# smoggie.net
KiCad netlist of a schematic drawn in EAGLE
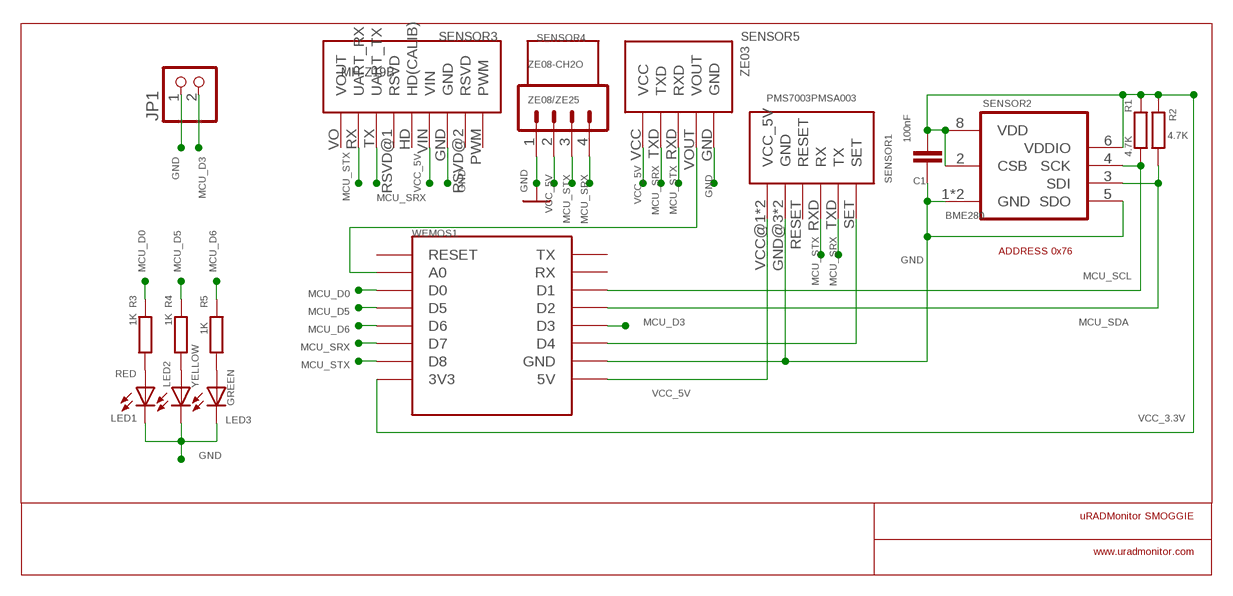
[diagram p0: schematic, sheet 1]

(export (version "E")
  (design (tool "Eeschema 10.0.6"))
  (components
    (comp (ref "C1")
      (value "100nF")
      (footprint "eagle-import:C0603")
      (libsource (lib "eagle-import") (part "C-EUC0603"))
    )
    (comp (ref "JP1")
      (value "PINHD-1X2")
      (footprint "eagle-import:1X02")
      (libsource (lib "eagle-import") (part "PINHD-1X2"))
    )
    (comp (ref "LED1")
      (value "RED")
      (footprint "eagle-import:SML0603")
      (libsource (lib "eagle-import") (part "LEDSML0603"))
    )
    (comp (ref "LED2")
      (value "YELLOW")
      (footprint "eagle-import:SML0603")
      (libsource (lib "eagle-import") (part "LEDSML0603"))
    )
    (comp (ref "LED3")
      (value "GREEN")
      (footprint "eagle-import:SML0603")
      (libsource (lib "eagle-import") (part "LEDSML0603"))
    )
    (comp (ref "R1")
      (value "4.7K")
      (footprint "eagle-import:R0603")
      (libsource (lib "eagle-import") (part "R-EU_R0603"))
    )
    (comp (ref "R2")
      (value "4.7K")
      (footprint "eagle-import:R0603")
      (libsource (lib "eagle-import") (part "R-EU_R0603"))
    )
    (comp (ref "R3")
      (value "1K")
      (footprint "eagle-import:R0603")
      (libsource (lib "eagle-import") (part "R-EU_R0603"))
    )
    (comp (ref "R4")
      (value "1K")
      (footprint "eagle-import:R0603")
      (libsource (lib "eagle-import") (part "R-EU_R0603"))
    )
    (comp (ref "R5")
      (value "1K")
      (footprint "eagle-import:R0603")
      (libsource (lib "eagle-import") (part "R-EU_R0603"))
    )
    (comp (ref "SENSOR1")
      (value "PMS7003PMSA003")
      (footprint "eagle-import:PMSA003")
      (libsource (lib "eagle-import") (part "PMS7003PMSA003"))
    )
    (comp (ref "SENSOR2")
      (value "BME280")
      (footprint "eagle-import:BME280")
      (libsource (lib "eagle-import") (part "BME280"))
    )
    (comp (ref "SENSOR3")
      (value "MH-Z19B")
      (footprint "eagle-import:MH-Z19B")
      (libsource (lib "eagle-import") (part "MH-Z19B"))
    )
    (comp (ref "SENSOR4")
      (value "ZE08-CH2O")
      (footprint "eagle-import:ZE08-CH2O_SENSOR")
      (libsource (lib "eagle-import") (part "ZE08-CH2O_SENSOR"))
    )
    (comp (ref "SENSOR5")
      (value "ZE03")
      (footprint "eagle-import:ZE03")
      (libsource (lib "eagle-import") (part "ZE03"))
    )
    (comp (ref "WEMOS1")
      (value "11")
      (footprint "eagle-import:WEMOS-D1-MINI")
      (libsource (lib "eagle-import") (part "WEMOS-D1-MINI"))
    )
    (comp (ref "ZE08/ZE25")
      (value "M041X04_NO_SILK")
      (footprint "eagle-import:1X04_NO_SILK")
      (libsource (lib "eagle-import") (part "M041X04_NO_SILK"))
    )
  )
  (nets
    (net (code "1") (name "/MCU_D0") (class "Default")
      (node (ref "R3") (pin "1") (pinfunction "1_1") (pintype "passive"))
      (node (ref "WEMOS1") (pin "D0") (pinfunction "D0_D0") (pintype "bidirectional"))
    )
    (net (code "2") (name "/MCU_D3") (class "Default")
      (node (ref "JP1") (pin "2") (pinfunction "2_2") (pintype "passive"))
      (node (ref "WEMOS1") (pin "D3") (pinfunction "D3_D3") (pintype "bidirectional"))
    )
    (net (code "3") (name "/MCU_D5") (class "Default")
      (node (ref "R4") (pin "1") (pinfunction "1_1") (pintype "passive"))
      (node (ref "WEMOS1") (pin "D5") (pinfunction "D5_D5") (pintype "bidirectional"))
    )
    (net (code "4") (name "/MCU_D6") (class "Default")
      (node (ref "R5") (pin "1") (pinfunction "1_1") (pintype "passive"))
      (node (ref "WEMOS1") (pin "D6") (pinfunction "D6_D6") (pintype "bidirectional"))
    )
    (net (code "5") (name "/MCU_SCL") (class "Default")
      (node (ref "R1") (pin "2") (pinfunction "2_2") (pintype "passive"))
      (node (ref "SENSOR2") (pin "4") (pinfunction "SCK_4") (pintype "bidirectional"))
      (node (ref "WEMOS1") (pin "D1") (pinfunction "D1_D1") (pintype "bidirectional"))
    )
    (net (code "6") (name "/MCU_SDA") (class "Default")
      (node (ref "R2") (pin "2") (pinfunction "2_2") (pintype "passive"))
      (node (ref "SENSOR2") (pin "3") (pinfunction "SDI_3") (pintype "bidirectional"))
      (node (ref "WEMOS1") (pin "D2") (pinfunction "D2_D2") (pintype "bidirectional"))
    )
    (net (code "7") (name "/MCU_SRX") (class "Default")
      (node (ref "SENSOR1") (pin "TXD") (pinfunction "TX_TXD") (pintype "bidirectional"))
      (node (ref "SENSOR3") (pin "TX") (pinfunction "UART_TX_TX") (pintype "bidirectional"))
      (node (ref "SENSOR5") (pin "TXD") (pinfunction "TXD_TXD") (pintype "bidirectional"))
      (node (ref "WEMOS1") (pin "D7") (pinfunction "D7_D7") (pintype "bidirectional"))
      (node (ref "ZE08/ZE25") (pin "4") (pinfunction "4_4") (pintype "passive"))
    )
    (net (code "8") (name "/MCU_STX") (class "Default")
      (node (ref "SENSOR1") (pin "RXD") (pinfunction "RX_RXD") (pintype "bidirectional"))
      (node (ref "SENSOR3") (pin "RX") (pinfunction "UART_RX_RX") (pintype "bidirectional"))
      (node (ref "SENSOR5") (pin "RXD") (pinfunction "RXD_RXD") (pintype "bidirectional"))
      (node (ref "WEMOS1") (pin "D8") (pinfunction "D8_D8") (pintype "bidirectional"))
      (node (ref "ZE08/ZE25") (pin "3") (pinfunction "3_3") (pintype "passive"))
    )
    (net (code "9") (name "/VCC_3.3V") (class "Default")
      (node (ref "C1") (pin "2") (pinfunction "2_2") (pintype "passive"))
      (node (ref "R1") (pin "1") (pinfunction "1_1") (pintype "passive"))
      (node (ref "R2") (pin "1") (pinfunction "1_1") (pintype "passive"))
      (node (ref "SENSOR2") (pin "2") (pinfunction "CSB_2") (pintype "input"))
      (node (ref "SENSOR2") (pin "6") (pinfunction "VDDIO_6") (pintype "power_in"))
      (node (ref "SENSOR2") (pin "8") (pinfunction "VDD_8") (pintype "power_in"))
      (node (ref "WEMOS1") (pin "3V3") (pinfunction "3V3_3V3") (pintype "bidirectional"))
    )
    (net (code "10") (name "/VCC_5V") (class "Default")
      (node (ref "SENSOR1") (pin "VCC@1") (pinfunction "VCC_5V_VCC@1") (pintype "bidirectional"))
      (node (ref "SENSOR1") (pin "VCC@2") (pinfunction "VCC_5V_VCC@2") (pintype "bidirectional"))
      (node (ref "SENSOR3") (pin "VIN") (pinfunction "VIN_VIN") (pintype "bidirectional"))
      (node (ref "SENSOR5") (pin "VCC") (pinfunction "VCC_VCC") (pintype "bidirectional"))
      (node (ref "WEMOS1") (pin "5V") (pinfunction "5V_5V") (pintype "bidirectional"))
      (node (ref "ZE08/ZE25") (pin "2") (pinfunction "2_2") (pintype "passive"))
    )
    (net (code "11") (name "GND") (class "Default")
      (node (ref "C1") (pin "1") (pinfunction "1_1") (pintype "passive"))
      (node (ref "JP1") (pin "1") (pinfunction "1_1") (pintype "passive"))
      (node (ref "LED1") (pin "C") (pinfunction "C_C") (pintype "passive"))
      (node (ref "LED2") (pin "C") (pinfunction "C_C") (pintype "passive"))
      (node (ref "LED3") (pin "C") (pinfunction "C_C") (pintype "passive"))
      (node (ref "SENSOR1") (pin "GND@3") (pinfunction "GND_GND@3") (pintype "bidirectional"))
      (node (ref "SENSOR1") (pin "GND@4") (pinfunction "GND_GND@4") (pintype "bidirectional"))
      (node (ref "SENSOR2") (pin "1") (pinfunction "GND_1") (pintype "power_in"))
      (node (ref "SENSOR2") (pin "5") (pinfunction "SDO_5") (pintype "input"))
      (node (ref "SENSOR2") (pin "7") (pinfunction "GND_7") (pintype "power_in"))
      (node (ref "SENSOR3") (pin "GND") (pinfunction "GND_GND") (pintype "bidirectional"))
      (node (ref "SENSOR5") (pin "GND") (pinfunction "GND_GND") (pintype "bidirectional"))
      (node (ref "WEMOS1") (pin "GND") (pinfunction "GND_GND") (pintype "bidirectional"))
      (node (ref "ZE08/ZE25") (pin "1") (pinfunction "1_1") (pintype "passive"))
    )
    (net (code "12") (name "Net-(LED1-PadA)") (class "Default")
      (node (ref "LED1") (pin "A") (pinfunction "A_A") (pintype "passive"))
      (node (ref "R3") (pin "2") (pinfunction "2_2") (pintype "passive"))
    )
    (net (code "13") (name "Net-(LED2-PadA)") (class "Default")
      (node (ref "LED2") (pin "A") (pinfunction "A_A") (pintype "passive"))
      (node (ref "R4") (pin "2") (pinfunction "2_2") (pintype "passive"))
    )
    (net (code "14") (name "Net-(LED3-PadA)") (class "Default")
      (node (ref "LED3") (pin "A") (pinfunction "A_A") (pintype "passive"))
      (node (ref "R5") (pin "2") (pinfunction "2_2") (pintype "passive"))
    )
    (net (code "15") (name "Net-(SENSOR1-PadSET)") (class "Default")
      (node (ref "SENSOR1") (pin "SET") (pinfunction "SET_SET") (pintype "bidirectional"))
      (node (ref "WEMOS1") (pin "D4") (pinfunction "D4_D4") (pintype "bidirectional"))
    )
    (net (code "16") (name "Net-(SENSOR5-PadVOUT)") (class "Default")
      (node (ref "SENSOR5") (pin "VOUT") (pinfunction "VOUT_VOUT") (pintype "bidirectional"))
      (node (ref "WEMOS1") (pin "A0") (pinfunction "A0_A0") (pintype "bidirectional"))
    )
    (net (code "17") (name "unconnected-(SENSOR1-PadRESET)") (class "Default")
      (node (ref "SENSOR1") (pin "RESET") (pinfunction "RESET_RESET") (pintype "bidirectional"))
    )
    (net (code "18") (name "unconnected-(SENSOR3-HD(CALIB)-PadHD)") (class "Default")
      (node (ref "SENSOR3") (pin "HD") (pinfunction "HD(CALIB)_HD") (pintype "bidirectional"))
    )
    (net (code "19") (name "unconnected-(SENSOR3-PadPWM)") (class "Default")
      (node (ref "SENSOR3") (pin "PWM") (pinfunction "PWM_PWM") (pintype "bidirectional"))
    )
    (net (code "20") (name "unconnected-(SENSOR3-RSVD-PadRSVD@1)") (class "Default")
      (node (ref "SENSOR3") (pin "RSVD@1") (pinfunction "RSVD_RSVD@1") (pintype "bidirectional"))
    )
    (net (code "21") (name "unconnected-(SENSOR3-RSVD-PadRSVD@2)") (class "Default")
      (node (ref "SENSOR3") (pin "RSVD@2") (pinfunction "RSVD_RSVD@2") (pintype "bidirectional"))
    )
    (net (code "22") (name "unconnected-(SENSOR3-VOUT-PadVO)") (class "Default")
      (node (ref "SENSOR3") (pin "VO") (pinfunction "VOUT_VO") (pintype "bidirectional"))
    )
    (net (code "23") (name "unconnected-(WEMOS1-PadRESET)") (class "Default")
      (node (ref "WEMOS1") (pin "RESET") (pinfunction "RESET_RESET") (pintype "bidirectional"))
    )
    (net (code "24") (name "unconnected-(WEMOS1-PadRX)") (class "Default")
      (node (ref "WEMOS1") (pin "RX") (pinfunction "RX_RX") (pintype "bidirectional"))
    )
    (net (code "25") (name "unconnected-(WEMOS1-PadTX)") (class "Default")
      (node (ref "WEMOS1") (pin "TX") (pinfunction "TX_TX") (pintype "bidirectional"))
    )
  )
)
